# DisplayReceiver_Microcontroller.net
KiCad netlist of a schematic drawn in Altium Designer
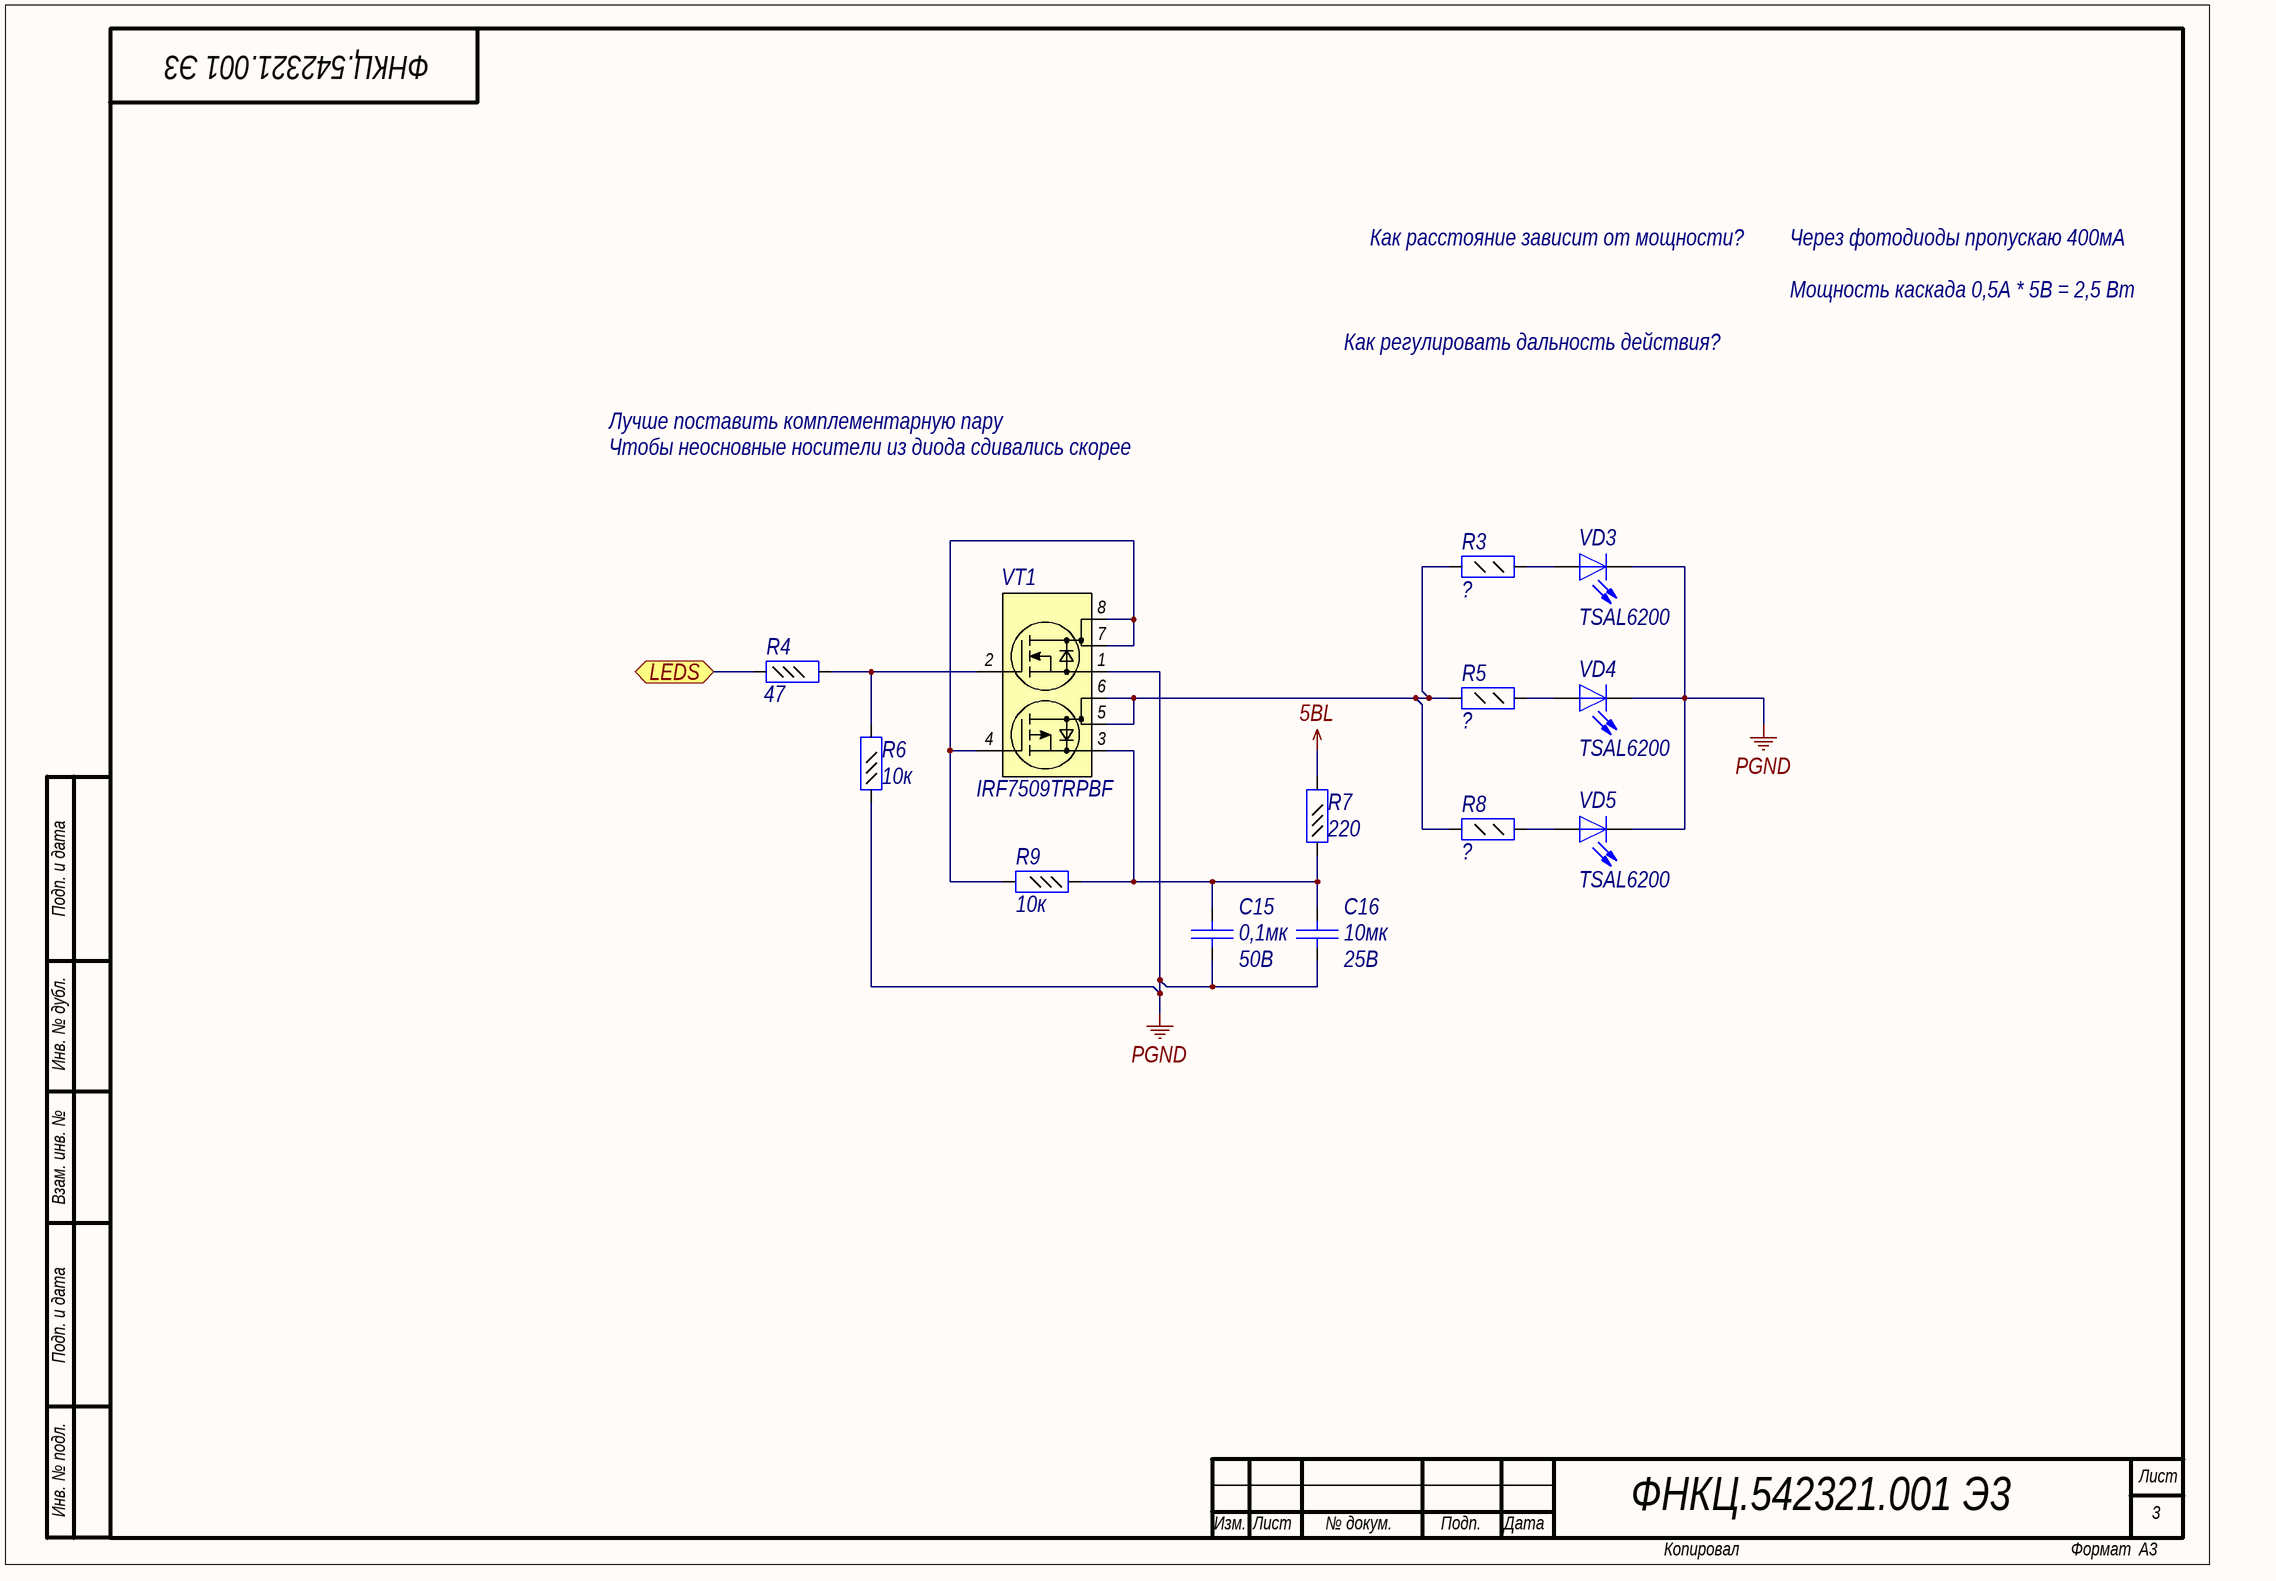
[diagram p0: DisplayReceiver_Microcontroller.SchDoc]

(export (version "E")
  (design (tool "Eeschema 10.0.6"))
  (components
    (comp (ref "C15")
      (value "0,1мк")
      (footprint "C0603")
      (description "Конденсатор")
      (fields
        (field (name "VOLTAGE") "50B")
        (field (name "PART NUMBER") "GRM188R71H104K")
        (field (name "Comment") "Capacitor")
      )
      (libsource (lib "MOP44") (part "Capacitor"))
    )
    (comp (ref "C16")
      (value "10мк")
      (footprint "C1210")
      (description "Конденсатор")
      (fields
        (field (name "VOLTAGE") "25В")
        (field (name "PART NUMBER") "GRM32ER61A106K")
        (field (name "Comment") "Capacitor")
      )
      (libsource (lib "MOP44") (part "Capacitor"))
    )
    (comp (ref "R3")
      (value "?")
      (footprint "R0805")
      (description "Резистор")
      (fields (field (name "PART NUMBER") "RC0805FR-0722RL") (field (name "POWER") "0,125Вт"))
      (libsource (lib "MOP44") (part "Resistor_0,125Вт"))
    )
    (comp (ref "R4")
      (value "47")
      (footprint "R0603")
      (description "Резистор")
      (fields (field (name "PART NUMBER") "RC0603FR-0747RL") (field (name "POWER") "0,062Вт"))
      (libsource (lib "") (part "Resistor_0,062Вт_1"))
    )
    (comp (ref "R5")
      (value "?")
      (footprint "R0805")
      (description "Резистор")
      (fields (field (name "PART NUMBER") "RC0805FR-0722RL") (field (name "POWER") "0,125Вт"))
      (libsource (lib "MOP44") (part "Resistor_0,125Вт"))
    )
    (comp (ref "R6")
      (value "10к")
      (footprint "R0603")
      (description "Резистор")
      (fields (field (name "PART NUMBER") "RC0603FR-0710KL") (field (name "POWER") "0,062Вт"))
      (libsource (lib "MOP44") (part "Resistor_0,062Вт"))
    )
    (comp (ref "R7")
      (value "220")
      (footprint "R0603")
      (description "Резистор")
      (fields (field (name "PART NUMBER") "RC0603FR-07220RL") (field (name "POWER") "0,062Вт"))
      (libsource (lib "MOP44") (part "Resistor_0,062Вт"))
    )
    (comp (ref "R8")
      (value "?")
      (footprint "R0805")
      (description "Резистор")
      (fields (field (name "PART NUMBER") "RC0805FR-0722RL") (field (name "POWER") "0,125Вт"))
      (libsource (lib "MOP44") (part "Resistor_0,125Вт"))
    )
    (comp (ref "R9")
      (value "10к")
      (footprint "R0603")
      (description "Резистор")
      (fields (field (name "PART NUMBER") "RC0603FR-0710KL") (field (name "POWER") "0,062Вт"))
      (libsource (lib "") (part "Resistor_0,062Вт_2"))
    )
    (comp (ref "VD3")
      (value "LED")
      (footprint "RADIAL_5MM")
      (description "Светодиод")
      (fields (field (name "PART NUMBER") "TSAL6200"))
      (libsource (lib "MOP44") (part "LED"))
    )
    (comp (ref "VD4")
      (value "LED")
      (footprint "RADIAL_5MM")
      (description "Светодиод")
      (fields (field (name "PART NUMBER") "TSAL6200"))
      (libsource (lib "MOP44") (part "LED"))
    )
    (comp (ref "VD5")
      (value "LED")
      (footprint "RADIAL_5MM")
      (description "Светодиод")
      (fields (field (name "PART NUMBER") "TSAL6200"))
      (libsource (lib "MOP44") (part "LED"))
    )
    (comp (ref "VT1")
      (value "IRF7509TRPBF")
      (footprint "Micro8")
      (description "Комплементарная сборка МОП")
      (fields (field (name "MANUFACTURER") "International Rectifier"))
      (libsource (lib "MOP44") (part "IRF7509TRPBF"))
    )
  )
  (nets
    (net (code "1") (name "/LEDS") (class "Default")
      (node (ref "R4") (pin "1") (pinfunction "1_1") (pintype "passive"))
    )
    (net (code "2") (name "5ВL") (class "Default")
      (node (ref "R7") (pin "2") (pinfunction "2_2") (pintype "passive"))
    )
    (net (code "3") (name "Net-(R3-Pad2)") (class "Default")
      (node (ref "R3") (pin "2") (pinfunction "2_2") (pintype "passive"))
      (node (ref "R5") (pin "2") (pinfunction "2_2") (pintype "passive"))
      (node (ref "R8") (pin "2") (pinfunction "2_2") (pintype "passive"))
      (node (ref "VT1") (pin "5") (pinfunction "D2_5") (pintype "passive"))
      (node (ref "VT1") (pin "6") (pinfunction "D2_6") (pintype "passive"))
    )
    (net (code "4") (name "Net-(VD3-A)") (class "Default")
      (node (ref "R3") (pin "1") (pinfunction "1_1") (pintype "passive"))
      (node (ref "VD3") (pin "2") (pinfunction "A_2") (pintype "passive"))
    )
    (net (code "5") (name "Net-(VD4-A)") (class "Default")
      (node (ref "R5") (pin "1") (pinfunction "1_1") (pintype "passive"))
      (node (ref "VD4") (pin "2") (pinfunction "A_2") (pintype "passive"))
    )
    (net (code "6") (name "Net-(VD5-A)") (class "Default")
      (node (ref "R8") (pin "1") (pinfunction "1_1") (pintype "passive"))
      (node (ref "VD5") (pin "2") (pinfunction "A_2") (pintype "passive"))
    )
    (net (code "7") (name "Net-(VT1-G1)") (class "Default")
      (node (ref "R4") (pin "2") (pinfunction "2_2") (pintype "passive"))
      (node (ref "R6") (pin "2") (pinfunction "2_2") (pintype "passive"))
      (node (ref "VT1") (pin "2") (pinfunction "G1_2") (pintype "passive"))
    )
    (net (code "8") (name "Net-(VT1-G2)") (class "Default")
      (node (ref "R9") (pin "2") (pinfunction "2_2") (pintype "passive"))
      (node (ref "VT1") (pin "4") (pinfunction "G2_4") (pintype "passive"))
      (node (ref "VT1") (pin "7") (pinfunction "D1_7") (pintype "passive"))
      (node (ref "VT1") (pin "8") (pinfunction "D1_8") (pintype "passive"))
    )
    (net (code "9") (name "Net-(VT1-S2)") (class "Default")
      (node (ref "C15") (pin "2") (pinfunction "2_2") (pintype "passive"))
      (node (ref "C16") (pin "2") (pinfunction "2_2") (pintype "passive"))
      (node (ref "R7") (pin "1") (pinfunction "1_1") (pintype "passive"))
      (node (ref "R9") (pin "1") (pinfunction "1_1") (pintype "passive"))
      (node (ref "VT1") (pin "3") (pinfunction "S2_3") (pintype "passive"))
    )
    (net (code "10") (name "PGND") (class "Default")
      (node (ref "C15") (pin "1") (pinfunction "1_1") (pintype "passive"))
      (node (ref "C16") (pin "1") (pinfunction "1_1") (pintype "passive"))
      (node (ref "R6") (pin "1") (pinfunction "1_1") (pintype "passive"))
      (node (ref "VD3") (pin "1") (pinfunction "K_1") (pintype "passive"))
      (node (ref "VD4") (pin "1") (pinfunction "K_1") (pintype "passive"))
      (node (ref "VD5") (pin "1") (pinfunction "K_1") (pintype "passive"))
      (node (ref "VT1") (pin "1") (pinfunction "S1_1") (pintype "passive"))
    )
  )
)
